# Mega_PCB.net
KiCad netlist of a schematic drawn in EAGLE
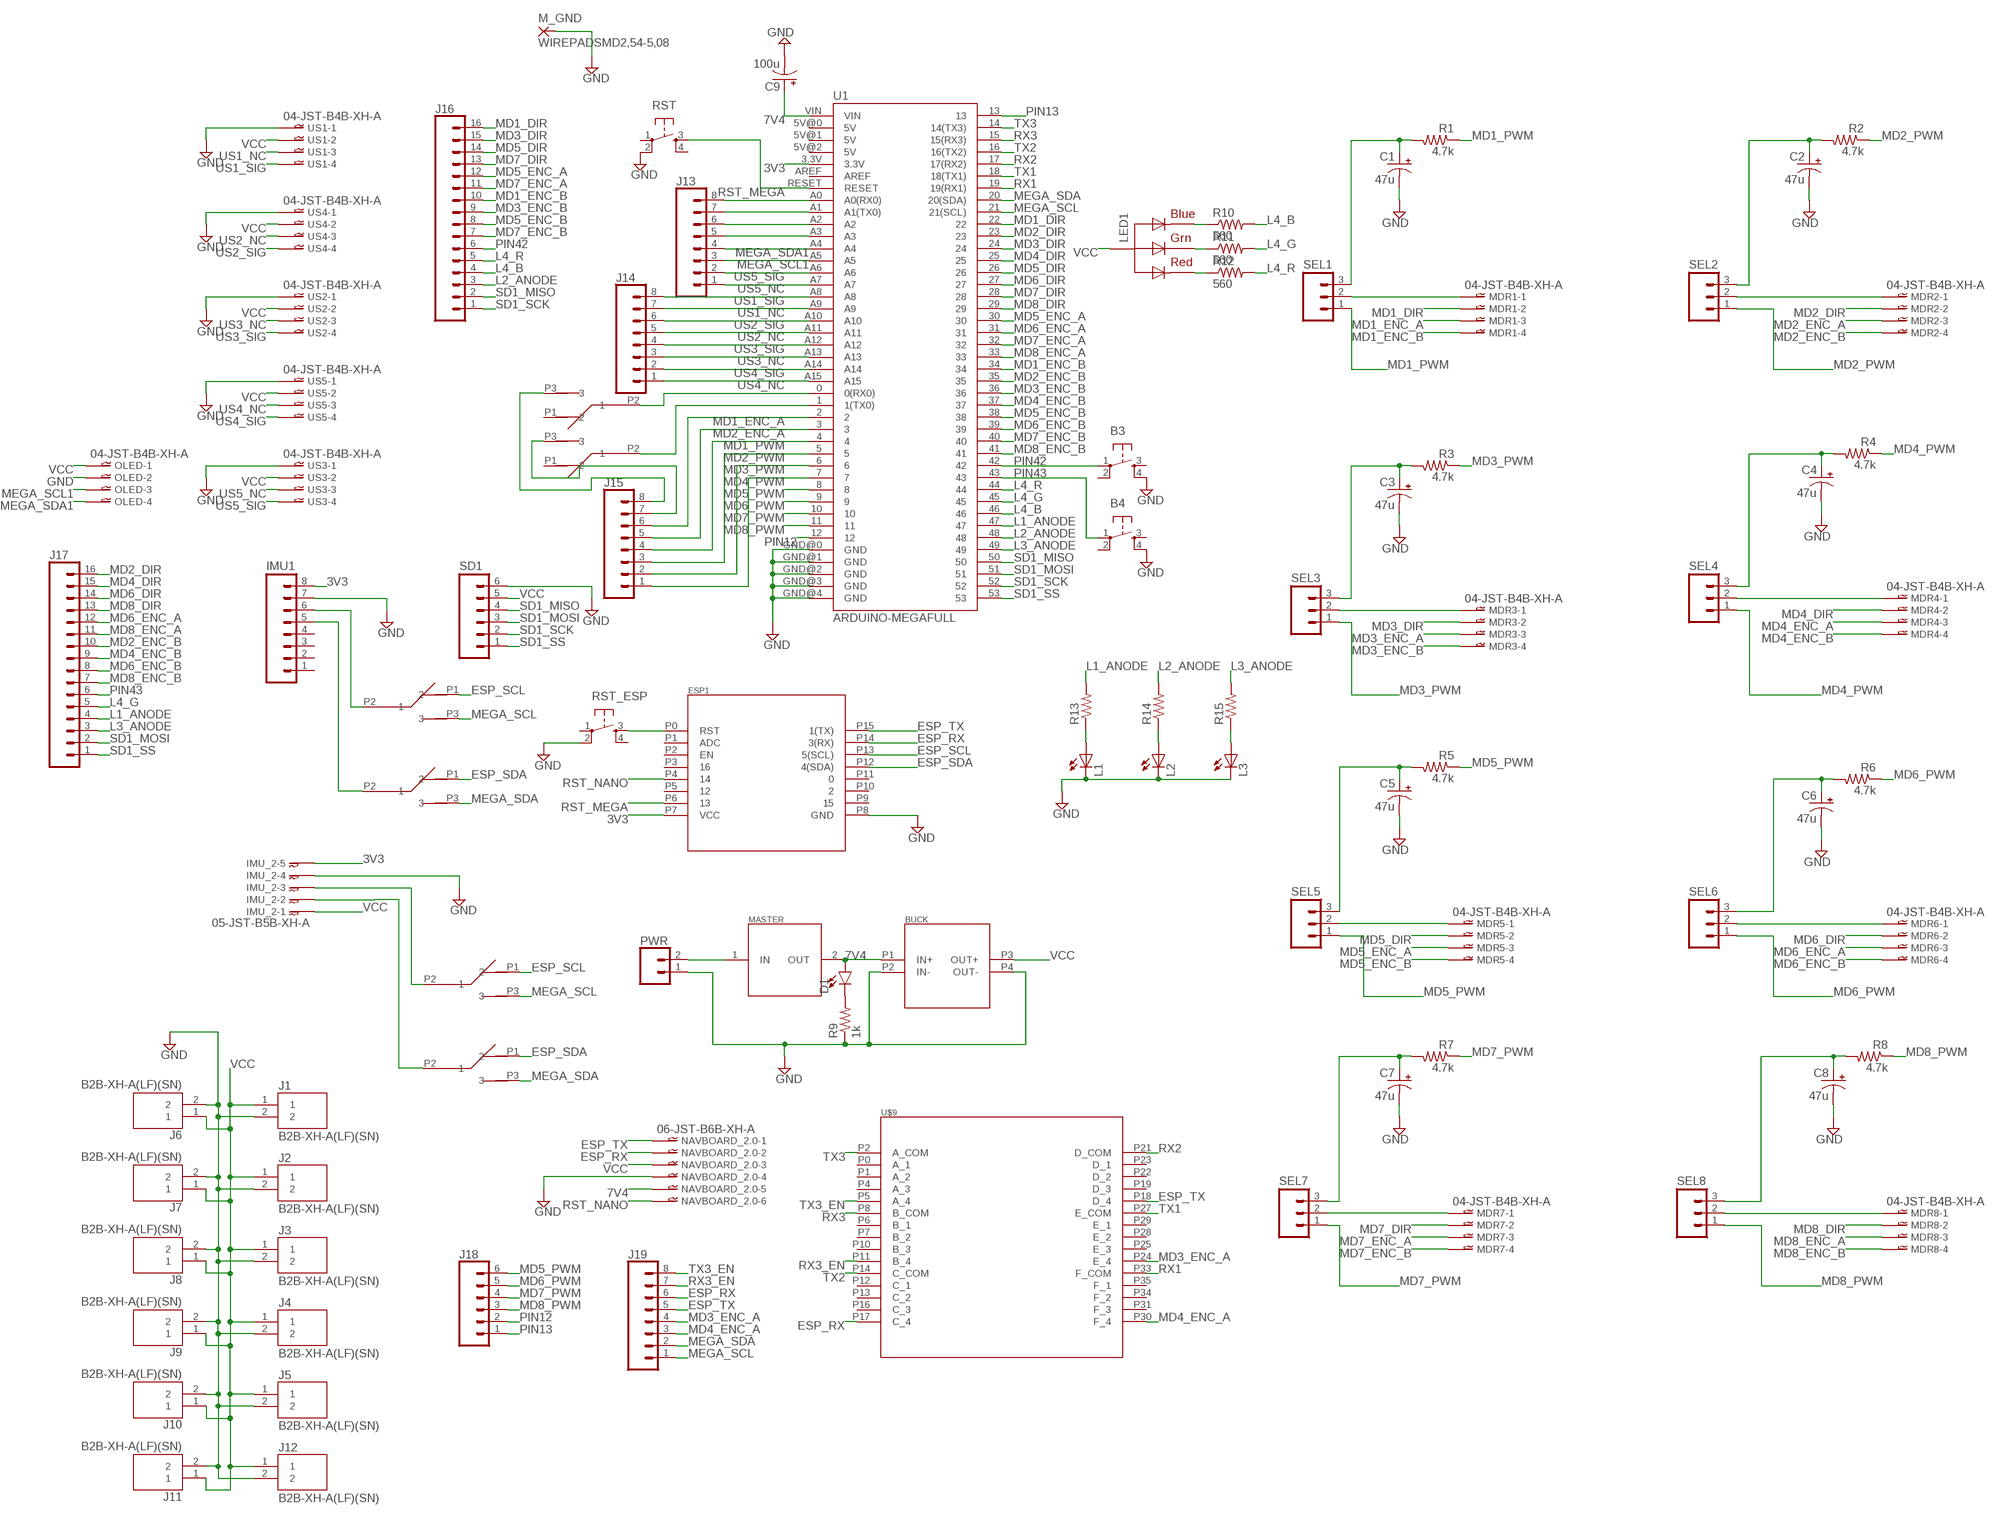
[diagram p0: schematic, sheet 1]

(export (version "E")
  (design (tool "Eeschema 10.0.6"))
  (components
    (comp (ref "B3")
      (value "TAC_SWITCHPTH")
      (footprint "eagle-import:TACTILE-PTH")
      (libsource (lib "eagle-import") (part "TAC_SWITCHPTH"))
    )
    (comp (ref "B4")
      (value "TAC_SWITCHPTH")
      (footprint "eagle-import:TACTILE-PTH")
      (libsource (lib "eagle-import") (part "TAC_SWITCHPTH"))
    )
    (comp (ref "BUCK")
      (value "5V_BUCK")
      (footprint "eagle-import:5V_BUCK")
      (libsource (lib "eagle-import") (part "5V_BUCK"))
    )
    (comp (ref "C1")
      (value "47u")
      (footprint "eagle-import:E2-5")
      (libsource (lib "eagle-import") (part "CPOL-USE2-5"))
    )
    (comp (ref "C2")
      (value "47u")
      (footprint "eagle-import:E2-5")
      (libsource (lib "eagle-import") (part "CPOL-USE2-5"))
    )
    (comp (ref "C3")
      (value "47u")
      (footprint "eagle-import:E2-5")
      (libsource (lib "eagle-import") (part "CPOL-USE2-5"))
    )
    (comp (ref "C4")
      (value "47u")
      (footprint "eagle-import:E2-5")
      (libsource (lib "eagle-import") (part "CPOL-USE2-5"))
    )
    (comp (ref "C5")
      (value "47u")
      (footprint "eagle-import:E2-5")
      (libsource (lib "eagle-import") (part "CPOL-USE2-5"))
    )
    (comp (ref "C6")
      (value "47u")
      (footprint "eagle-import:E2-5")
      (libsource (lib "eagle-import") (part "CPOL-USE2-5"))
    )
    (comp (ref "C7")
      (value "47u")
      (footprint "eagle-import:E2-5")
      (libsource (lib "eagle-import") (part "CPOL-USE2-5"))
    )
    (comp (ref "C8")
      (value "47u")
      (footprint "eagle-import:E2-5")
      (libsource (lib "eagle-import") (part "CPOL-USE2-5"))
    )
    (comp (ref "C9")
      (value "100u")
      (footprint "eagle-import:TT2D6")
      (libsource (lib "eagle-import") (part "CPOL-USTT2D6"))
    )
    (comp (ref "D1")
      (value "LED5MM")
      (footprint "eagle-import:LED_5MM")
      (libsource (lib "eagle-import") (part "LED5MM"))
    )
    (comp (ref "ESP1")
      (value "ESP07")
      (footprint "eagle-import:ESP07")
      (libsource (lib "eagle-import") (part "ESP07"))
    )
    (comp (ref "IMU1")
      (value "M081X08")
      (footprint "eagle-import:1X08")
      (libsource (lib "eagle-import") (part "M081X08"))
    )
    (comp (ref "IMU1_SCL_SEL")
      (value "SLIDE_SWITCH")
      (footprint "eagle-import:SLIDE_SWITCH")
      (libsource (lib "eagle-import") (part "SLIDE_SWITCH"))
    )
    (comp (ref "IMU1_SDA_SEL")
      (value "SLIDE_SWITCH")
      (footprint "eagle-import:SLIDE_SWITCH")
      (libsource (lib "eagle-import") (part "SLIDE_SWITCH"))
    )
    (comp (ref "IMU2_SCL_SEL")
      (value "SLIDE_SWITCH")
      (footprint "eagle-import:SLIDE_SWITCH")
      (libsource (lib "eagle-import") (part "SLIDE_SWITCH"))
    )
    (comp (ref "IMU2_SDA_SEL")
      (value "SLIDE_SWITCH")
      (footprint "eagle-import:SLIDE_SWITCH")
      (libsource (lib "eagle-import") (part "SLIDE_SWITCH"))
    )
    (comp (ref "IMU_2")
      (value "05-JST-B5B-XH-A")
      (footprint "eagle-import:B5B-XH")
      (libsource (lib "eagle-import") (part "05-JST-B5B-XH-A"))
    )
    (comp (ref "J1")
      (value "B2B-XH-A(LF)(SN)")
      (footprint "eagle-import:JST_B2B-XH-A(LF)(SN)")
      (fields (field (name "MF") "JST Sales"))
      (libsource (lib "eagle-import") (part "B2B-XH-A(LF)(SN)"))
    )
    (comp (ref "J2")
      (value "B2B-XH-A(LF)(SN)")
      (footprint "eagle-import:JST_B2B-XH-A(LF)(SN)")
      (fields (field (name "MF") "JST Sales"))
      (libsource (lib "eagle-import") (part "B2B-XH-A(LF)(SN)"))
    )
    (comp (ref "J3")
      (value "B2B-XH-A(LF)(SN)")
      (footprint "eagle-import:JST_B2B-XH-A(LF)(SN)")
      (fields (field (name "MF") "JST Sales"))
      (libsource (lib "eagle-import") (part "B2B-XH-A(LF)(SN)"))
    )
    (comp (ref "J4")
      (value "B2B-XH-A(LF)(SN)")
      (footprint "eagle-import:JST_B2B-XH-A(LF)(SN)")
      (fields (field (name "MF") "JST Sales"))
      (libsource (lib "eagle-import") (part "B2B-XH-A(LF)(SN)"))
    )
    (comp (ref "J5")
      (value "B2B-XH-A(LF)(SN)")
      (footprint "eagle-import:JST_B2B-XH-A(LF)(SN)")
      (fields (field (name "MF") "JST Sales"))
      (libsource (lib "eagle-import") (part "B2B-XH-A(LF)(SN)"))
    )
    (comp (ref "J6")
      (value "B2B-XH-A(LF)(SN)")
      (footprint "eagle-import:JST_B2B-XH-A(LF)(SN)")
      (fields (field (name "MF") "JST Sales"))
      (libsource (lib "eagle-import") (part "B2B-XH-A(LF)(SN)"))
    )
    (comp (ref "J7")
      (value "B2B-XH-A(LF)(SN)")
      (footprint "eagle-import:JST_B2B-XH-A(LF)(SN)")
      (fields (field (name "MF") "JST Sales"))
      (libsource (lib "eagle-import") (part "B2B-XH-A(LF)(SN)"))
    )
    (comp (ref "J8")
      (value "B2B-XH-A(LF)(SN)")
      (footprint "eagle-import:JST_B2B-XH-A(LF)(SN)")
      (fields (field (name "MF") "JST Sales"))
      (libsource (lib "eagle-import") (part "B2B-XH-A(LF)(SN)"))
    )
    (comp (ref "J9")
      (value "B2B-XH-A(LF)(SN)")
      (footprint "eagle-import:JST_B2B-XH-A(LF)(SN)")
      (fields (field (name "MF") "JST Sales"))
      (libsource (lib "eagle-import") (part "B2B-XH-A(LF)(SN)"))
    )
    (comp (ref "J10")
      (value "B2B-XH-A(LF)(SN)")
      (footprint "eagle-import:JST_B2B-XH-A(LF)(SN)")
      (fields (field (name "MF") "JST Sales"))
      (libsource (lib "eagle-import") (part "B2B-XH-A(LF)(SN)"))
    )
    (comp (ref "J11")
      (value "B2B-XH-A(LF)(SN)")
      (footprint "eagle-import:JST_B2B-XH-A(LF)(SN)")
      (fields (field (name "MF") "JST Sales"))
      (libsource (lib "eagle-import") (part "B2B-XH-A(LF)(SN)"))
    )
    (comp (ref "J12")
      (value "B2B-XH-A(LF)(SN)")
      (footprint "eagle-import:JST_B2B-XH-A(LF)(SN)")
      (fields (field (name "MF") "JST Sales"))
      (libsource (lib "eagle-import") (part "B2B-XH-A(LF)(SN)"))
    )
    (comp (ref "J13")
      (value "CONN_08\"")
      (footprint "eagle-import:1X08")
      (libsource (lib "eagle-import") (part "CONN_08{dblquote}"))
    )
    (comp (ref "J14")
      (value "CONN_08\"")
      (footprint "eagle-import:1X08")
      (libsource (lib "eagle-import") (part "CONN_08{dblquote}"))
    )
    (comp (ref "J15")
      (value "CONN_08\"")
      (footprint "eagle-import:1X08")
      (libsource (lib "eagle-import") (part "CONN_08{dblquote}"))
    )
    (comp (ref "J16")
      (value "CONN_16")
      (footprint "eagle-import:1X16")
      (libsource (lib "eagle-import") (part "CONN_16"))
    )
    (comp (ref "J17")
      (value "CONN_16")
      (footprint "eagle-import:1X16")
      (libsource (lib "eagle-import") (part "CONN_16"))
    )
    (comp (ref "J18")
      (value "CONN_06SILK_FEMALE_PTH")
      (footprint "eagle-import:1X06")
      (libsource (lib "eagle-import") (part "CONN_06SILK_FEMALE_PTH"))
    )
    (comp (ref "J19")
      (value "CONN_08\"")
      (footprint "eagle-import:1X08")
      (libsource (lib "eagle-import") (part "CONN_08{dblquote}"))
    )
    (comp (ref "L1")
      (value "LED3MM")
      (footprint "eagle-import:LED3MM")
      (libsource (lib "eagle-import") (part "adafruit_420_LED3MM"))
    )
    (comp (ref "L2")
      (value "LED3MM")
      (footprint "eagle-import:LED3MM")
      (libsource (lib "eagle-import") (part "adafruit_420_LED3MM"))
    )
    (comp (ref "L3")
      (value "LED3MM")
      (footprint "eagle-import:LED3MM")
      (libsource (lib "eagle-import") (part "adafruit_420_LED3MM"))
    )
    (comp (ref "LED1")
      (value "RGBLED_CA-5MM")
      (footprint "eagle-import:LED5MMRGB")
      (libsource (lib "eagle-import") (part "RGBLED_CA-5MM"))
    )
    (comp (ref "MASTER")
      (value "MED_SWITCH")
      (footprint "eagle-import:MED_SWITCH")
      (libsource (lib "eagle-import") (part "MED_SWITCH"))
    )
    (comp (ref "MDR1")
      (value "04-JST-B4B-XH-A")
      (footprint "eagle-import:B4B-XH")
      (libsource (lib "eagle-import") (part "04-JST-B4B-XH-A"))
    )
    (comp (ref "MDR2")
      (value "04-JST-B4B-XH-A")
      (footprint "eagle-import:B4B-XH")
      (libsource (lib "eagle-import") (part "04-JST-B4B-XH-A"))
    )
    (comp (ref "MDR3")
      (value "04-JST-B4B-XH-A")
      (footprint "eagle-import:B4B-XH")
      (libsource (lib "eagle-import") (part "04-JST-B4B-XH-A"))
    )
    (comp (ref "MDR4")
      (value "04-JST-B4B-XH-A")
      (footprint "eagle-import:B4B-XH")
      (libsource (lib "eagle-import") (part "04-JST-B4B-XH-A"))
    )
    (comp (ref "MDR5")
      (value "04-JST-B4B-XH-A")
      (footprint "eagle-import:B4B-XH")
      (libsource (lib "eagle-import") (part "04-JST-B4B-XH-A"))
    )
    (comp (ref "MDR6")
      (value "04-JST-B4B-XH-A")
      (footprint "eagle-import:B4B-XH")
      (libsource (lib "eagle-import") (part "04-JST-B4B-XH-A"))
    )
    (comp (ref "MDR7")
      (value "04-JST-B4B-XH-A")
      (footprint "eagle-import:B4B-XH")
      (libsource (lib "eagle-import") (part "04-JST-B4B-XH-A"))
    )
    (comp (ref "MDR8")
      (value "04-JST-B4B-XH-A")
      (footprint "eagle-import:B4B-XH")
      (libsource (lib "eagle-import") (part "04-JST-B4B-XH-A"))
    )
    (comp (ref "M_GND")
      (value "WIREPADSMD2,54-5,08")
      (footprint "eagle-import:SMD2,54-5,08")
      (libsource (lib "eagle-import") (part "WIREPADSMD2,54-5,08"))
    )
    (comp (ref "NAVBOARD_2.0")
      (value "06-JST-B6B-XH-A")
      (footprint "eagle-import:B6B-XH")
      (libsource (lib "eagle-import") (part "06-JST-B6B-XH-A"))
    )
    (comp (ref "OLED")
      (value "04-JST-B4B-XH-A")
      (footprint "eagle-import:B4B-XH")
      (libsource (lib "eagle-import") (part "04-JST-B4B-XH-A"))
    )
    (comp (ref "PWR")
      (value "CONN_02PTH4")
      (footprint "eagle-import:1X02_XTRA_BIG")
      (libsource (lib "eagle-import") (part "CONN_02PTH4"))
    )
    (comp (ref "R1")
      (value "4.7k")
      (footprint "eagle-import:0204_7")
      (libsource (lib "eagle-import") (part "R-US_0204/7"))
    )
    (comp (ref "R2")
      (value "4.7k")
      (footprint "eagle-import:0204_7")
      (libsource (lib "eagle-import") (part "R-US_0204/7"))
    )
    (comp (ref "R3")
      (value "4.7k")
      (footprint "eagle-import:0204_7")
      (libsource (lib "eagle-import") (part "R-US_0204/7"))
    )
    (comp (ref "R4")
      (value "4.7k")
      (footprint "eagle-import:0204_7")
      (libsource (lib "eagle-import") (part "R-US_0204/7"))
    )
    (comp (ref "R5")
      (value "4.7k")
      (footprint "eagle-import:0204_7")
      (libsource (lib "eagle-import") (part "R-US_0204/7"))
    )
    (comp (ref "R6")
      (value "4.7k")
      (footprint "eagle-import:0204_7")
      (libsource (lib "eagle-import") (part "R-US_0204/7"))
    )
    (comp (ref "R7")
      (value "4.7k")
      (footprint "eagle-import:0204_7")
      (libsource (lib "eagle-import") (part "R-US_0204/7"))
    )
    (comp (ref "R8")
      (value "4.7k")
      (footprint "eagle-import:0204_7")
      (libsource (lib "eagle-import") (part "R-US_0204/7"))
    )
    (comp (ref "R9")
      (value "1k")
      (footprint "eagle-import:0204_7")
      (libsource (lib "eagle-import") (part "R-US_0204/7"))
    )
    (comp (ref "R10")
      (value "560")
      (footprint "eagle-import:0204_7")
      (libsource (lib "eagle-import") (part "R-US_0204/7"))
    )
    (comp (ref "R11")
      (value "560")
      (footprint "eagle-import:0204_7")
      (libsource (lib "eagle-import") (part "R-US_0204/7"))
    )
    (comp (ref "R12")
      (value "560")
      (footprint "eagle-import:0204_7")
      (libsource (lib "eagle-import") (part "R-US_0204/7"))
    )
    (comp (ref "R13")
      (value "R-US_0204/7")
      (footprint "eagle-import:0204_7")
      (libsource (lib "eagle-import") (part "R-US_0204/7"))
    )
    (comp (ref "R14")
      (value "R-US_0204/7")
      (footprint "eagle-import:0204_7")
      (libsource (lib "eagle-import") (part "R-US_0204/7"))
    )
    (comp (ref "R15")
      (value "R-US_0204/7")
      (footprint "eagle-import:0204_7")
      (libsource (lib "eagle-import") (part "R-US_0204/7"))
    )
    (comp (ref "RST")
      (value "TAC_SWITCHPTH")
      (footprint "eagle-import:TACTILE-PTH")
      (libsource (lib "eagle-import") (part "TAC_SWITCHPTH"))
    )
    (comp (ref "RST_ESP")
      (value "TAC_SWITCHPTH")
      (footprint "eagle-import:TACTILE-PTH")
      (libsource (lib "eagle-import") (part "TAC_SWITCHPTH"))
    )
    (comp (ref "SD1")
      (value "M06SIP")
      (footprint "eagle-import:1X06")
      (libsource (lib "eagle-import") (part "M06SIP"))
    )
    (comp (ref "SEL1")
      (value "M03PTH")
      (footprint "eagle-import:1X03")
      (libsource (lib "eagle-import") (part "M03PTH"))
    )
    (comp (ref "SEL2")
      (value "M03PTH")
      (footprint "eagle-import:1X03")
      (libsource (lib "eagle-import") (part "M03PTH"))
    )
    (comp (ref "SEL3")
      (value "M03PTH")
      (footprint "eagle-import:1X03")
      (libsource (lib "eagle-import") (part "M03PTH"))
    )
    (comp (ref "SEL4")
      (value "M03PTH")
      (footprint "eagle-import:1X03")
      (libsource (lib "eagle-import") (part "M03PTH"))
    )
    (comp (ref "SEL5")
      (value "M03PTH")
      (footprint "eagle-import:1X03")
      (libsource (lib "eagle-import") (part "M03PTH"))
    )
    (comp (ref "SEL6")
      (value "M03PTH")
      (footprint "eagle-import:1X03")
      (libsource (lib "eagle-import") (part "M03PTH"))
    )
    (comp (ref "SEL7")
      (value "M03PTH")
      (footprint "eagle-import:1X03")
      (libsource (lib "eagle-import") (part "M03PTH"))
    )
    (comp (ref "SEL8")
      (value "M03PTH")
      (footprint "eagle-import:1X03")
      (libsource (lib "eagle-import") (part "M03PTH"))
    )
    (comp (ref "U$3")
      (value "SLIDE_SWITCH")
      (footprint "eagle-import:SLIDE_SWITCH")
      (libsource (lib "eagle-import") (part "SLIDE_SWITCH"))
    )
    (comp (ref "U$4")
      (value "SLIDE_SWITCH")
      (footprint "eagle-import:SLIDE_SWITCH")
      (libsource (lib "eagle-import") (part "SLIDE_SWITCH"))
    )
    (comp (ref "U$9")
      (value "CATERPILLAR")
      (footprint "eagle-import:CATERPILLAR")
      (libsource (lib "eagle-import") (part "CATERPILLAR"))
    )
    (comp (ref "U1")
      (value "ARDUINO-MEGAFULL")
      (footprint "eagle-import:ARDUINO_MEGA")
      (libsource (lib "eagle-import") (part "ARDUINO-MEGAFULL"))
    )
    (comp (ref "US1")
      (value "04-JST-B4B-XH-A")
      (footprint "eagle-import:B4B-XH")
      (libsource (lib "eagle-import") (part "04-JST-B4B-XH-A"))
    )
    (comp (ref "US2")
      (value "04-JST-B4B-XH-A")
      (footprint "eagle-import:B4B-XH")
      (libsource (lib "eagle-import") (part "04-JST-B4B-XH-A"))
    )
    (comp (ref "US3")
      (value "04-JST-B4B-XH-A")
      (footprint "eagle-import:B4B-XH")
      (libsource (lib "eagle-import") (part "04-JST-B4B-XH-A"))
    )
    (comp (ref "US4")
      (value "04-JST-B4B-XH-A")
      (footprint "eagle-import:B4B-XH")
      (libsource (lib "eagle-import") (part "04-JST-B4B-XH-A"))
    )
    (comp (ref "US5")
      (value "04-JST-B4B-XH-A")
      (footprint "eagle-import:B4B-XH")
      (libsource (lib "eagle-import") (part "04-JST-B4B-XH-A"))
    )
  )
  (nets
    (net (code "1") (name "/3V3") (class "Default")
      (node (ref "ESP1") (pin "P7") (pinfunction "VCC_P7") (pintype "bidirectional"))
      (node (ref "IMU1") (pin "8") (pinfunction "8_8") (pintype "passive"))
      (node (ref "IMU_2") (pin "P$5") (pinfunction "1_P$5") (pintype "passive"))
      (node (ref "U1") (pin "3.3V") (pinfunction "3.3V_3.3V") (pintype "bidirectional"))
    )
    (net (code "2") (name "/7V4") (class "Default")
      (node (ref "BUCK") (pin "P1") (pinfunction "IN+_P1") (pintype "bidirectional"))
      (node (ref "C9") (pin "+") (pinfunction "+_+") (pintype "passive"))
      (node (ref "D1") (pin "A") (pinfunction "A_A") (pintype "passive"))
      (node (ref "MASTER") (pin "2") (pinfunction "OUT_2") (pintype "bidirectional"))
      (node (ref "NAVBOARD_2.0") (pin "P$5") (pinfunction "1_P$5") (pintype "passive"))
      (node (ref "U1") (pin "VIN") (pinfunction "VIN_VIN") (pintype "bidirectional"))
    )
    (net (code "3") (name "/ESP_RX") (class "Default")
      (node (ref "ESP1") (pin "P14") (pinfunction "3(RX)_P14") (pintype "bidirectional"))
      (node (ref "J19") (pin "6") (pinfunction "6_6") (pintype "passive"))
      (node (ref "NAVBOARD_2.0") (pin "P$2") (pinfunction "1_P$2") (pintype "passive"))
      (node (ref "U$9") (pin "P17") (pinfunction "C_4_P17") (pintype "bidirectional"))
    )
    (net (code "4") (name "/ESP_SCL") (class "Default")
      (node (ref "ESP1") (pin "P13") (pinfunction "5(SCL)_P13") (pintype "bidirectional"))
      (node (ref "IMU1_SCL_SEL") (pin "P1") (pinfunction "2_P1") (pintype "bidirectional"))
      (node (ref "IMU2_SCL_SEL") (pin "P1") (pinfunction "2_P1") (pintype "bidirectional"))
    )
    (net (code "5") (name "/ESP_SDA") (class "Default")
      (node (ref "ESP1") (pin "P12") (pinfunction "4(SDA)_P12") (pintype "bidirectional"))
      (node (ref "IMU1_SDA_SEL") (pin "P1") (pinfunction "2_P1") (pintype "bidirectional"))
      (node (ref "IMU2_SDA_SEL") (pin "P1") (pinfunction "2_P1") (pintype "bidirectional"))
    )
    (net (code "6") (name "/ESP_TX") (class "Default")
      (node (ref "ESP1") (pin "P15") (pinfunction "1(TX)_P15") (pintype "bidirectional"))
      (node (ref "J19") (pin "5") (pinfunction "5_5") (pintype "passive"))
      (node (ref "NAVBOARD_2.0") (pin "P$1") (pinfunction "1_P$1") (pintype "passive"))
      (node (ref "U$9") (pin "P18") (pinfunction "D_4_P18") (pintype "bidirectional"))
    )
    (net (code "7") (name "/L1_ANODE") (class "Default")
      (node (ref "J17") (pin "4") (pinfunction "4_4") (pintype "passive"))
      (node (ref "R13") (pin "2") (pinfunction "2_2") (pintype "passive"))
      (node (ref "U1") (pin "47") (pinfunction "47_47") (pintype "bidirectional"))
    )
    (net (code "8") (name "/L2_ANODE") (class "Default")
      (node (ref "J16") (pin "3") (pinfunction "3_3") (pintype "passive"))
      (node (ref "R14") (pin "2") (pinfunction "2_2") (pintype "passive"))
      (node (ref "U1") (pin "48") (pinfunction "48_48") (pintype "bidirectional"))
    )
    (net (code "9") (name "/L3_ANODE") (class "Default")
      (node (ref "J17") (pin "3") (pinfunction "3_3") (pintype "passive"))
      (node (ref "R15") (pin "2") (pinfunction "2_2") (pintype "passive"))
      (node (ref "U1") (pin "49") (pinfunction "49_49") (pintype "bidirectional"))
    )
    (net (code "10") (name "/L4_B") (class "Default")
      (node (ref "J16") (pin "4") (pinfunction "4_4") (pintype "passive"))
      (node (ref "R10") (pin "2") (pinfunction "2_2") (pintype "passive"))
      (node (ref "U1") (pin "46") (pinfunction "46_46") (pintype "bidirectional"))
    )
    (net (code "11") (name "/L4_G") (class "Default")
      (node (ref "J17") (pin "5") (pinfunction "5_5") (pintype "passive"))
      (node (ref "R11") (pin "2") (pinfunction "2_2") (pintype "passive"))
      (node (ref "U1") (pin "45") (pinfunction "45_45") (pintype "bidirectional"))
    )
    (net (code "12") (name "/L4_R") (class "Default")
      (node (ref "J16") (pin "5") (pinfunction "5_5") (pintype "passive"))
      (node (ref "R12") (pin "2") (pinfunction "2_2") (pintype "passive"))
      (node (ref "U1") (pin "44") (pinfunction "44_44") (pintype "bidirectional"))
    )
    (net (code "13") (name "/MD1_DIR") (class "Default")
      (node (ref "J16") (pin "16") (pinfunction "16_16") (pintype "passive"))
      (node (ref "MDR1") (pin "P$2") (pinfunction "1_P$2") (pintype "passive"))
      (node (ref "U1") (pin "22") (pinfunction "22_22") (pintype "bidirectional"))
    )
    (net (code "14") (name "/MD1_ENC_A") (class "Default")
      (node (ref "J15") (pin "6") (pinfunction "6_6") (pintype "passive"))
      (node (ref "MDR1") (pin "P$3") (pinfunction "1_P$3") (pintype "passive"))
      (node (ref "U1") (pin "2") (pinfunction "2_2") (pintype "bidirectional"))
    )
    (net (code "15") (name "/MD1_ENC_B") (class "Default")
      (node (ref "J16") (pin "10") (pinfunction "10_10") (pintype "passive"))
      (node (ref "MDR1") (pin "P$4") (pinfunction "1_P$4") (pintype "passive"))
      (node (ref "U1") (pin "34") (pinfunction "34_34") (pintype "bidirectional"))
    )
    (net (code "16") (name "/MD1_PWM") (class "Default")
      (node (ref "J15") (pin "4") (pinfunction "4_4") (pintype "passive"))
      (node (ref "R1") (pin "1") (pinfunction "1_1") (pintype "passive"))
      (node (ref "SEL1") (pin "1") (pinfunction "1_1") (pintype "passive"))
      (node (ref "U1") (pin "4") (pinfunction "4_4") (pintype "bidirectional"))
    )
    (net (code "17") (name "/MD2_DIR") (class "Default")
      (node (ref "J17") (pin "16") (pinfunction "16_16") (pintype "passive"))
      (node (ref "MDR2") (pin "P$2") (pinfunction "1_P$2") (pintype "passive"))
      (node (ref "U1") (pin "23") (pinfunction "23_23") (pintype "bidirectional"))
    )
    (net (code "18") (name "/MD2_ENC_A") (class "Default")
      (node (ref "J15") (pin "5") (pinfunction "5_5") (pintype "passive"))
      (node (ref "MDR2") (pin "P$3") (pinfunction "1_P$3") (pintype "passive"))
      (node (ref "U1") (pin "3") (pinfunction "3_3") (pintype "bidirectional"))
    )
    (net (code "19") (name "/MD2_ENC_B") (class "Default")
      (node (ref "J17") (pin "10") (pinfunction "10_10") (pintype "passive"))
      (node (ref "MDR2") (pin "P$4") (pinfunction "1_P$4") (pintype "passive"))
      (node (ref "U1") (pin "35") (pinfunction "35_35") (pintype "bidirectional"))
    )
    (net (code "20") (name "/MD2_PWM") (class "Default")
      (node (ref "J15") (pin "3") (pinfunction "3_3") (pintype "passive"))
      (node (ref "R2") (pin "1") (pinfunction "1_1") (pintype "passive"))
      (node (ref "SEL2") (pin "1") (pinfunction "1_1") (pintype "passive"))
      (node (ref "U1") (pin "5") (pinfunction "5_5") (pintype "bidirectional"))
    )
    (net (code "21") (name "/MD3_DIR") (class "Default")
      (node (ref "J16") (pin "15") (pinfunction "15_15") (pintype "passive"))
      (node (ref "MDR3") (pin "P$2") (pinfunction "1_P$2") (pintype "passive"))
      (node (ref "U1") (pin "24") (pinfunction "24_24") (pintype "bidirectional"))
    )
    (net (code "22") (name "/MD3_ENC_A") (class "Default")
      (node (ref "J19") (pin "4") (pinfunction "4_4") (pintype "passive"))
      (node (ref "MDR3") (pin "P$3") (pinfunction "1_P$3") (pintype "passive"))
      (node (ref "U$9") (pin "P24") (pinfunction "E_4_P24") (pintype "bidirectional"))
    )
    (net (code "23") (name "/MD3_ENC_B") (class "Default")
      (node (ref "J16") (pin "9") (pinfunction "9_9") (pintype "passive"))
      (node (ref "MDR3") (pin "P$4") (pinfunction "1_P$4") (pintype "passive"))
      (node (ref "U1") (pin "36") (pinfunction "36_36") (pintype "bidirectional"))
    )
    (net (code "24") (name "/MD3_PWM") (class "Default")
      (node (ref "J15") (pin "2") (pinfunction "2_2") (pintype "passive"))
      (node (ref "R3") (pin "1") (pinfunction "1_1") (pintype "passive"))
      (node (ref "SEL3") (pin "1") (pinfunction "1_1") (pintype "passive"))
      (node (ref "U1") (pin "6") (pinfunction "6_6") (pintype "bidirectional"))
    )
    (net (code "25") (name "/MD4_DIR") (class "Default")
      (node (ref "J17") (pin "15") (pinfunction "15_15") (pintype "passive"))
      (node (ref "MDR4") (pin "P$2") (pinfunction "1_P$2") (pintype "passive"))
      (node (ref "U1") (pin "25") (pinfunction "25_25") (pintype "bidirectional"))
    )
    (net (code "26") (name "/MD4_ENC_A") (class "Default")
      (node (ref "J19") (pin "3") (pinfunction "3_3") (pintype "passive"))
      (node (ref "MDR4") (pin "P$3") (pinfunction "1_P$3") (pintype "passive"))
      (node (ref "U$9") (pin "P30") (pinfunction "F_4_P30") (pintype "bidirectional"))
    )
    (net (code "27") (name "/MD4_ENC_B") (class "Default")
      (node (ref "J17") (pin "9") (pinfunction "9_9") (pintype "passive"))
      (node (ref "MDR4") (pin "P$4") (pinfunction "1_P$4") (pintype "passive"))
      (node (ref "U1") (pin "37") (pinfunction "37_37") (pintype "bidirectional"))
    )
    (net (code "28") (name "/MD4_PWM") (class "Default")
      (node (ref "J15") (pin "1") (pinfunction "1_1") (pintype "passive"))
      (node (ref "R4") (pin "1") (pinfunction "1_1") (pintype "passive"))
      (node (ref "SEL4") (pin "1") (pinfunction "1_1") (pintype "passive"))
      (node (ref "U1") (pin "7") (pinfunction "7_7") (pintype "bidirectional"))
    )
    (net (code "29") (name "/MD5_DIR") (class "Default")
      (node (ref "J16") (pin "14") (pinfunction "14_14") (pintype "passive"))
      (node (ref "MDR5") (pin "P$2") (pinfunction "1_P$2") (pintype "passive"))
      (node (ref "U1") (pin "26") (pinfunction "26_26") (pintype "bidirectional"))
    )
    (net (code "30") (name "/MD5_ENC_A") (class "Default")
      (node (ref "J16") (pin "12") (pinfunction "12_12") (pintype "passive"))
      (node (ref "MDR5") (pin "P$3") (pinfunction "1_P$3") (pintype "passive"))
      (node (ref "U1") (pin "30") (pinfunction "30_30") (pintype "bidirectional"))
    )
    (net (code "31") (name "/MD5_ENC_B") (class "Default")
      (node (ref "J16") (pin "8") (pinfunction "8_8") (pintype "passive"))
      (node (ref "MDR5") (pin "P$4") (pinfunction "1_P$4") (pintype "passive"))
      (node (ref "U1") (pin "38") (pinfunction "38_38") (pintype "bidirectional"))
    )
    (net (code "32") (name "/MD5_PWM") (class "Default")
      (node (ref "J18") (pin "6") (pinfunction "6_6") (pintype "passive"))
      (node (ref "R5") (pin "1") (pinfunction "1_1") (pintype "passive"))
      (node (ref "SEL5") (pin "1") (pinfunction "1_1") (pintype "passive"))
      (node (ref "U1") (pin "8") (pinfunction "8_8") (pintype "bidirectional"))
    )
    (net (code "33") (name "/MD6_DIR") (class "Default")
      (node (ref "J17") (pin "14") (pinfunction "14_14") (pintype "passive"))
      (node (ref "MDR6") (pin "P$2") (pinfunction "1_P$2") (pintype "passive"))
      (node (ref "U1") (pin "27") (pinfunction "27_27") (pintype "bidirectional"))
    )
    (net (code "34") (name "/MD6_ENC_A") (class "Default")
      (node (ref "J17") (pin "12") (pinfunction "12_12") (pintype "passive"))
      (node (ref "MDR6") (pin "P$3") (pinfunction "1_P$3") (pintype "passive"))
      (node (ref "U1") (pin "31") (pinfunction "31_31") (pintype "bidirectional"))
    )
    (net (code "35") (name "/MD6_ENC_B") (class "Default")
      (node (ref "J17") (pin "8") (pinfunction "8_8") (pintype "passive"))
      (node (ref "MDR6") (pin "P$4") (pinfunction "1_P$4") (pintype "passive"))
      (node (ref "U1") (pin "39") (pinfunction "39_39") (pintype "bidirectional"))
    )
    (net (code "36") (name "/MD6_PWM") (class "Default")
      (node (ref "J18") (pin "5") (pinfunction "5_5") (pintype "passive"))
      (node (ref "R6") (pin "1") (pinfunction "1_1") (pintype "passive"))
      (node (ref "SEL6") (pin "1") (pinfunction "1_1") (pintype "passive"))
      (node (ref "U1") (pin "9") (pinfunction "9_9") (pintype "bidirectional"))
    )
    (net (code "37") (name "/MD7_DIR") (class "Default")
      (node (ref "J16") (pin "13") (pinfunction "13_13") (pintype "passive"))
      (node (ref "MDR7") (pin "P$2") (pinfunction "1_P$2") (pintype "passive"))
      (node (ref "U1") (pin "28") (pinfunction "28_28") (pintype "bidirectional"))
    )
    (net (code "38") (name "/MD7_ENC_A") (class "Default")
      (node (ref "J16") (pin "11") (pinfunction "11_11") (pintype "passive"))
      (node (ref "MDR7") (pin "P$3") (pinfunction "1_P$3") (pintype "passive"))
      (node (ref "U1") (pin "32") (pinfunction "32_32") (pintype "bidirectional"))
    )
    (net (code "39") (name "/MD7_ENC_B") (class "Default")
      (node (ref "J16") (pin "7") (pinfunction "7_7") (pintype "passive"))
      (node (ref "MDR7") (pin "P$4") (pinfunction "1_P$4") (pintype "passive"))
      (node (ref "U1") (pin "40") (pinfunction "40_40") (pintype "bidirectional"))
    )
    (net (code "40") (name "/MD7_PWM") (class "Default")
      (node (ref "J18") (pin "4") (pinfunction "4_4") (pintype "passive"))
      (node (ref "R7") (pin "1") (pinfunction "1_1") (pintype "passive"))
      (node (ref "SEL7") (pin "1") (pinfunction "1_1") (pintype "passive"))
      (node (ref "U1") (pin "10") (pinfunction "10_10") (pintype "bidirectional"))
    )
    (net (code "41") (name "/MD8_DIR") (class "Default")
      (node (ref "J17") (pin "13") (pinfunction "13_13") (pintype "passive"))
      (node (ref "MDR8") (pin "P$2") (pinfunction "1_P$2") (pintype "passive"))
      (node (ref "U1") (pin "29") (pinfunction "29_29") (pintype "bidirectional"))
    )
    (net (code "42") (name "/MD8_ENC_A") (class "Default")
      (node (ref "J17") (pin "11") (pinfunction "11_11") (pintype "passive"))
      (node (ref "MDR8") (pin "P$3") (pinfunction "1_P$3") (pintype "passive"))
      (node (ref "U1") (pin "33") (pinfunction "33_33") (pintype "bidirectional"))
    )
    (net (code "43") (name "/MD8_ENC_B") (class "Default")
      (node (ref "J17") (pin "7") (pinfunction "7_7") (pintype "passive"))
      (node (ref "MDR8") (pin "P$4") (pinfunction "1_P$4") (pintype "passive"))
      (node (ref "U1") (pin "41") (pinfunction "41_41") (pintype "bidirectional"))
    )
    (net (code "44") (name "/MD8_PWM") (class "Default")
      (node (ref "J18") (pin "3") (pinfunction "3_3") (pintype "passive"))
      (node (ref "R8") (pin "1") (pinfunction "1_1") (pintype "passive"))
      (node (ref "SEL8") (pin "1") (pinfunction "1_1") (pintype "passive"))
      (node (ref "U1") (pin "11") (pinfunction "11_11") (pintype "bidirectional"))
    )
    (net (code "45") (name "/MEGA_SCL") (class "Default")
      (node (ref "IMU1_SCL_SEL") (pin "P3") (pinfunction "3_P3") (pintype "bidirectional"))
      (node (ref "IMU2_SCL_SEL") (pin "P3") (pinfunction "3_P3") (pintype "bidirectional"))
      (node (ref "J19") (pin "1") (pinfunction "1_1") (pintype "passive"))
      (node (ref "U1") (pin "21") (pinfunction "21(SCL)_21") (pintype "bidirectional"))
    )
    (net (code "46") (name "/MEGA_SCL1") (class "Default")
      (node (ref "J13") (pin "3") (pinfunction "3_3") (pintype "passive"))
      (node (ref "OLED") (pin "P$3") (pinfunction "1_P$3") (pintype "passive"))
      (node (ref "U1") (pin "A5") (pinfunction "A5_A5") (pintype "bidirectional"))
    )
    (net (code "47") (name "/MEGA_SDA") (class "Default")
      (node (ref "IMU1_SDA_SEL") (pin "P3") (pinfunction "3_P3") (pintype "bidirectional"))
      (node (ref "IMU2_SDA_SEL") (pin "P3") (pinfunction "3_P3") (pintype "bidirectional"))
      (node (ref "J19") (pin "2") (pinfunction "2_2") (pintype "passive"))
      (node (ref "U1") (pin "20") (pinfunction "20(SDA)_20") (pintype "bidirectional"))
    )
    (net (code "48") (name "/MEGA_SDA1") (class "Default")
      (node (ref "J13") (pin "4") (pinfunction "4_4") (pintype "passive"))
      (node (ref "OLED") (pin "P$4") (pinfunction "1_P$4") (pintype "passive"))
      (node (ref "U1") (pin "A4") (pinfunction "A4_A4") (pintype "bidirectional"))
    )
    (net (code "49") (name "/PIN12") (class "Default")
      (node (ref "J18") (pin "2") (pinfunction "2_2") (pintype "passive"))
      (node (ref "U1") (pin "12") (pinfunction "12_12") (pintype "bidirectional"))
    )
    (net (code "50") (name "/PIN13") (class "Default")
      (node (ref "J18") (pin "1") (pinfunction "1_1") (pintype "passive"))
      (node (ref "U1") (pin "13") (pinfunction "13_13") (pintype "bidirectional"))
    )
    (net (code "51") (name "/PIN42") (class "Default")
      (node (ref "B3") (pin "1") (pinfunction "1_1") (pintype "passive"))
      (node (ref "J16") (pin "6") (pinfunction "6_6") (pintype "passive"))
      (node (ref "U1") (pin "42") (pinfunction "42_42") (pintype "bidirectional"))
    )
    (net (code "52") (name "/PIN43") (class "Default")
      (node (ref "B4") (pin "1") (pinfunction "1_1") (pintype "passive"))
      (node (ref "J17") (pin "6") (pinfunction "6_6") (pintype "passive"))
      (node (ref "U1") (pin "43") (pinfunction "43_43") (pintype "bidirectional"))
    )
    (net (code "53") (name "/RST_MEGA") (class "Default")
      (node (ref "ESP1") (pin "P6") (pinfunction "13_P6") (pintype "bidirectional"))
      (node (ref "RST") (pin "3") (pinfunction "3_3") (pintype "passive"))
      (node (ref "U1") (pin "RESET") (pinfunction "RESET_RESET") (pintype "bidirectional"))
    )
    (net (code "54") (name "/RST_NANO") (class "Default")
      (node (ref "ESP1") (pin "P4") (pinfunction "14_P4") (pintype "bidirectional"))
      (node (ref "NAVBOARD_2.0") (pin "P$6") (pinfunction "1_P$6") (pintype "passive"))
    )
    (net (code "55") (name "/RX1") (class "Default")
      (node (ref "U$9") (pin "P33") (pinfunction "F_COM_P33") (pintype "bidirectional"))
      (node (ref "U1") (pin "19") (pinfunction "19(RX1)_19") (pintype "bidirectional"))
    )
    (net (code "56") (name "/RX2") (class "Default")
      (node (ref "U$9") (pin "P21") (pinfunction "D_COM_P21") (pintype "bidirectional"))
      (node (ref "U1") (pin "17") (pinfunction "17(RX2)_17") (pintype "bidirectional"))
    )
    (net (code "57") (name "/RX3") (class "Default")
      (node (ref "U$9") (pin "P8") (pinfunction "B_COM_P8") (pintype "bidirectional"))
      (node (ref "U1") (pin "15") (pinfunction "15(RX3)_15") (pintype "bidirectional"))
    )
    (net (code "58") (name "/RX3_EN") (class "Default")
      (node (ref "J19") (pin "7") (pinfunction "7_7") (pintype "passive"))
      (node (ref "U$9") (pin "P11") (pinfunction "B_4_P11") (pintype "bidirectional"))
    )
    (net (code "59") (name "/SD1_MISO") (class "Default")
      (node (ref "J16") (pin "2") (pinfunction "2_2") (pintype "passive"))
      (node (ref "SD1") (pin "4") (pinfunction "4_4") (pintype "passive"))
      (node (ref "U1") (pin "50") (pinfunction "50_50") (pintype "bidirectional"))
    )
    (net (code "60") (name "/SD1_MOSI") (class "Default")
      (node (ref "J17") (pin "2") (pinfunction "2_2") (pintype "passive"))
      (node (ref "SD1") (pin "3") (pinfunction "3_3") (pintype "passive"))
      (node (ref "U1") (pin "51") (pinfunction "51_51") (pintype "bidirectional"))
    )
    (net (code "61") (name "/SD1_SCK") (class "Default")
      (node (ref "J16") (pin "1") (pinfunction "1_1") (pintype "passive"))
      (node (ref "SD1") (pin "2") (pinfunction "2_2") (pintype "passive"))
      (node (ref "U1") (pin "52") (pinfunction "52_52") (pintype "bidirectional"))
    )
    (net (code "62") (name "/SD1_SS") (class "Default")
      (node (ref "J17") (pin "1") (pinfunction "1_1") (pintype "passive"))
      (node (ref "SD1") (pin "1") (pinfunction "1_1") (pintype "passive"))
      (node (ref "U1") (pin "53") (pinfunction "53_53") (pintype "bidirectional"))
    )
    (net (code "63") (name "/TX1") (class "Default")
      (node (ref "U$9") (pin "P27") (pinfunction "E_COM_P27") (pintype "bidirectional"))
      (node (ref "U1") (pin "18") (pinfunction "18(TX1)_18") (pintype "bidirectional"))
    )
    (net (code "64") (name "/TX2") (class "Default")
      (node (ref "U$9") (pin "P14") (pinfunction "C_COM_P14") (pintype "bidirectional"))
      (node (ref "U1") (pin "16") (pinfunction "16(TX2)_16") (pintype "bidirectional"))
    )
    (net (code "65") (name "/TX3") (class "Default")
      (node (ref "U$9") (pin "P2") (pinfunction "A_COM_P2") (pintype "bidirectional"))
      (node (ref "U1") (pin "14") (pinfunction "14(TX3)_14") (pintype "bidirectional"))
    )
    (net (code "66") (name "/TX3_EN") (class "Default")
      (node (ref "J19") (pin "8") (pinfunction "8_8") (pintype "passive"))
      (node (ref "U$9") (pin "P5") (pinfunction "A_4_P5") (pintype "bidirectional"))
    )
    (net (code "67") (name "/US1_NC") (class "Default")
      (node (ref "J14") (pin "7") (pinfunction "7_7") (pintype "passive"))
      (node (ref "U1") (pin "A9") (pinfunction "A9_A9") (pintype "bidirectional"))
      (node (ref "US1") (pin "P$3") (pinfunction "1_P$3") (pintype "passive"))
    )
    (net (code "68") (name "/US1_SIG") (class "Default")
      (node (ref "J14") (pin "8") (pinfunction "8_8") (pintype "passive"))
      (node (ref "U1") (pin "A8") (pinfunction "A8_A8") (pintype "bidirectional"))
      (node (ref "US1") (pin "P$4") (pinfunction "1_P$4") (pintype "passive"))
    )
    (net (code "69") (name "/US2_NC") (class "Default")
      (node (ref "J14") (pin "5") (pinfunction "5_5") (pintype "passive"))
      (node (ref "U1") (pin "A11") (pinfunction "A11_A11") (pintype "bidirectional"))
      (node (ref "US4") (pin "P$3") (pinfunction "1_P$3") (pintype "passive"))
    )
    (net (code "70") (name "/US2_SIG") (class "Default")
      (node (ref "J14") (pin "6") (pinfunction "6_6") (pintype "passive"))
      (node (ref "U1") (pin "A10") (pinfunction "A10_A10") (pintype "bidirectional"))
      (node (ref "US4") (pin "P$4") (pinfunction "1_P$4") (pintype "passive"))
    )
    (net (code "71") (name "/US3_NC") (class "Default")
      (node (ref "J14") (pin "3") (pinfunction "3_3") (pintype "passive"))
      (node (ref "U1") (pin "A13") (pinfunction "A13_A13") (pintype "bidirectional"))
      (node (ref "US2") (pin "P$3") (pinfunction "1_P$3") (pintype "passive"))
    )
    (net (code "72") (name "/US3_SIG") (class "Default")
      (node (ref "J14") (pin "4") (pinfunction "4_4") (pintype "passive"))
      (node (ref "U1") (pin "A12") (pinfunction "A12_A12") (pintype "bidirectional"))
      (node (ref "US2") (pin "P$4") (pinfunction "1_P$4") (pintype "passive"))
    )
    (net (code "73") (name "/US4_NC") (class "Default")
      (node (ref "J14") (pin "1") (pinfunction "1_1") (pintype "passive"))
      (node (ref "U1") (pin "A15") (pinfunction "A15_A15") (pintype "bidirectional"))
      (node (ref "US5") (pin "P$3") (pinfunction "1_P$3") (pintype "passive"))
    )
    (net (code "74") (name "/US4_SIG") (class "Default")
      (node (ref "J14") (pin "2") (pinfunction "2_2") (pintype "passive"))
      (node (ref "U1") (pin "A14") (pinfunction "A14_A14") (pintype "bidirectional"))
      (node (ref "US5") (pin "P$4") (pinfunction "1_P$4") (pintype "passive"))
    )
    (net (code "75") (name "/US5_NC") (class "Default")
      (node (ref "J13") (pin "1") (pinfunction "1_1") (pintype "passive"))
      (node (ref "U1") (pin "A7") (pinfunction "A7_A7") (pintype "bidirectional"))
      (node (ref "US3") (pin "P$3") (pinfunction "1_P$3") (pintype "passive"))
    )
    (net (code "76") (name "/US5_SIG") (class "Default")
      (node (ref "J13") (pin "2") (pinfunction "2_2") (pintype "passive"))
      (node (ref "U1") (pin "A6") (pinfunction "A6_A6") (pintype "bidirectional"))
      (node (ref "US3") (pin "P$4") (pinfunction "1_P$4") (pintype "passive"))
    )
    (net (code "77") (name "/VCC") (class "Default")
      (node (ref "BUCK") (pin "P3") (pinfunction "OUT+_P3") (pintype "bidirectional"))
      (node (ref "IMU_2") (pin "P$1") (pinfunction "1_P$1") (pintype "passive"))
      (node (ref "J1") (pin "1") (pinfunction "1_1") (pintype "passive"))
      (node (ref "J10") (pin "1") (pinfunction "1_1") (pintype "passive"))
      (node (ref "J11") (pin "1") (pinfunction "1_1") (pintype "passive"))
      (node (ref "J12") (pin "1") (pinfunction "1_1") (pintype "passive"))
      (node (ref "J2") (pin "1") (pinfunction "1_1") (pintype "passive"))
      (node (ref "J3") (pin "1") (pinfunction "1_1") (pintype "passive"))
      (node (ref "J4") (pin "1") (pinfunction "1_1") (pintype "passive"))
      (node (ref "J5") (pin "1") (pinfunction "1_1") (pintype "passive"))
      (node (ref "J6") (pin "1") (pinfunction "1_1") (pintype "passive"))
      (node (ref "J7") (pin "1") (pinfunction "1_1") (pintype "passive"))
      (node (ref "J8") (pin "1") (pinfunction "1_1") (pintype "passive"))
      (node (ref "J9") (pin "1") (pinfunction "1_1") (pintype "passive"))
      (node (ref "LED1") (pin "2") (pinfunction "VCC_2") (pintype "bidirectional"))
      (node (ref "NAVBOARD_2.0") (pin "P$3") (pinfunction "1_P$3") (pintype "passive"))
      (node (ref "OLED") (pin "P$1") (pinfunction "1_P$1") (pintype "passive"))
      (node (ref "SD1") (pin "5") (pinfunction "5_5") (pintype "passive"))
      (node (ref "US1") (pin "P$2") (pinfunction "1_P$2") (pintype "passive"))
      (node (ref "US2") (pin "P$2") (pinfunction "1_P$2") (pintype "passive"))
      (node (ref "US3") (pin "P$2") (pinfunction "1_P$2") (pintype "passive"))
      (node (ref "US4") (pin "P$2") (pinfunction "1_P$2") (pintype "passive"))
      (node (ref "US5") (pin "P$2") (pinfunction "1_P$2") (pintype "passive"))
    )
    (net (code "78") (name "GND") (class "Default")
      (node (ref "B3") (pin "4") (pinfunction "4_4") (pintype "passive"))
      (node (ref "B4") (pin "4") (pinfunction "4_4") (pintype "passive"))
      (node (ref "BUCK") (pin "P2") (pinfunction "IN-_P2") (pintype "bidirectional"))
      (node (ref "BUCK") (pin "P4") (pinfunction "OUT-_P4") (pintype "bidirectional"))
      (node (ref "C1") (pin "-") (pinfunction "-_-") (pintype "passive"))
      (node (ref "C2") (pin "-") (pinfunction "-_-") (pintype "passive"))
      (node (ref "C3") (pin "-") (pinfunction "-_-") (pintype "passive"))
      (node (ref "C4") (pin "-") (pinfunction "-_-") (pintype "passive"))
      (node (ref "C5") (pin "-") (pinfunction "-_-") (pintype "passive"))
      (node (ref "C6") (pin "-") (pinfunction "-_-") (pintype "passive"))
      (node (ref "C7") (pin "-") (pinfunction "-_-") (pintype "passive"))
      (node (ref "C8") (pin "-") (pinfunction "-_-") (pintype "passive"))
      (node (ref "C9") (pin "-") (pinfunction "-_-") (pintype "passive"))
      (node (ref "ESP1") (pin "P8") (pinfunction "GND_P8") (pintype "bidirectional"))
      (node (ref "IMU1") (pin "7") (pinfunction "7_7") (pintype "passive"))
      (node (ref "IMU_2") (pin "P$4") (pinfunction "1_P$4") (pintype "passive"))
      (node (ref "J1") (pin "2") (pinfunction "2_2") (pintype "passive"))
      (node (ref "J10") (pin "2") (pinfunction "2_2") (pintype "passive"))
      (node (ref "J11") (pin "2") (pinfunction "2_2") (pintype "passive"))
      (node (ref "J12") (pin "2") (pinfunction "2_2") (pintype "passive"))
      (node (ref "J2") (pin "2") (pinfunction "2_2") (pintype "passive"))
      (node (ref "J3") (pin "2") (pinfunction "2_2") (pintype "passive"))
      (node (ref "J4") (pin "2") (pinfunction "2_2") (pintype "passive"))
      (node (ref "J5") (pin "2") (pinfunction "2_2") (pintype "passive"))
      (node (ref "J6") (pin "2") (pinfunction "2_2") (pintype "passive"))
      (node (ref "J7") (pin "2") (pinfunction "2_2") (pintype "passive"))
      (node (ref "J8") (pin "2") (pinfunction "2_2") (pintype "passive"))
      (node (ref "J9") (pin "2") (pinfunction "2_2") (pintype "passive"))
      (node (ref "L1") (pin "K") (pinfunction "C_K") (pintype "passive"))
      (node (ref "L2") (pin "K") (pinfunction "C_K") (pintype "passive"))
      (node (ref "L3") (pin "K") (pinfunction "C_K") (pintype "passive"))
      (node (ref "M_GND") (pin "1") (pinfunction "P_1") (pintype "passive"))
      (node (ref "NAVBOARD_2.0") (pin "P$4") (pinfunction "1_P$4") (pintype "passive"))
      (node (ref "OLED") (pin "P$2") (pinfunction "1_P$2") (pintype "passive"))
      (node (ref "PWR") (pin "1") (pinfunction "1_1") (pintype "passive"))
      (node (ref "R9") (pin "1") (pinfunction "1_1") (pintype "passive"))
      (node (ref "RST") (pin "2") (pinfunction "2_2") (pintype "passive"))
      (node (ref "RST_ESP") (pin "2") (pinfunction "2_2") (pintype "passive"))
      (node (ref "SD1") (pin "6") (pinfunction "6_6") (pintype "passive"))
      (node (ref "U1") (pin "GND@0") (pinfunction "GND_GND@0") (pintype "bidirectional"))
      (node (ref "U1") (pin "GND@1") (pinfunction "GND_GND@1") (pintype "bidirectional"))
      (node (ref "U1") (pin "GND@2") (pinfunction "GND_GND@2") (pintype "bidirectional"))
      (node (ref "U1") (pin "GND@3") (pinfunction "GND_GND@3") (pintype "bidirectional"))
      (node (ref "U1") (pin "GND@4") (pinfunction "GND_GND@4") (pintype "bidirectional"))
      (node (ref "US1") (pin "P$1") (pinfunction "1_P$1") (pintype "passive"))
      (node (ref "US2") (pin "P$1") (pinfunction "1_P$1") (pintype "passive"))
      (node (ref "US3") (pin "P$1") (pinfunction "1_P$1") (pintype "passive"))
      (node (ref "US4") (pin "P$1") (pinfunction "1_P$1") (pintype "passive"))
      (node (ref "US5") (pin "P$1") (pinfunction "1_P$1") (pintype "passive"))
    )
    (net (code "79") (name "Net-(C1-Pad+)") (class "Default")
      (node (ref "C1") (pin "+") (pinfunction "+_+") (pintype "passive"))
      (node (ref "R1") (pin "2") (pinfunction "2_2") (pintype "passive"))
      (node (ref "SEL1") (pin "3") (pinfunction "3_3") (pintype "passive"))
    )
    (net (code "80") (name "Net-(C2-Pad+)") (class "Default")
      (node (ref "C2") (pin "+") (pinfunction "+_+") (pintype "passive"))
      (node (ref "R2") (pin "2") (pinfunction "2_2") (pintype "passive"))
      (node (ref "SEL2") (pin "3") (pinfunction "3_3") (pintype "passive"))
    )
    (net (code "81") (name "Net-(C3-Pad+)") (class "Default")
      (node (ref "C3") (pin "+") (pinfunction "+_+") (pintype "passive"))
      (node (ref "R3") (pin "2") (pinfunction "2_2") (pintype "passive"))
      (node (ref "SEL3") (pin "3") (pinfunction "3_3") (pintype "passive"))
    )
    (net (code "82") (name "Net-(C4-Pad+)") (class "Default")
      (node (ref "C4") (pin "+") (pinfunction "+_+") (pintype "passive"))
      (node (ref "R4") (pin "2") (pinfunction "2_2") (pintype "passive"))
      (node (ref "SEL4") (pin "3") (pinfunction "3_3") (pintype "passive"))
    )
    (net (code "83") (name "Net-(C5-Pad+)") (class "Default")
      (node (ref "C5") (pin "+") (pinfunction "+_+") (pintype "passive"))
      (node (ref "R5") (pin "2") (pinfunction "2_2") (pintype "passive"))
      (node (ref "SEL5") (pin "3") (pinfunction "3_3") (pintype "passive"))
    )
    (net (code "84") (name "Net-(C6-Pad+)") (class "Default")
      (node (ref "C6") (pin "+") (pinfunction "+_+") (pintype "passive"))
      (node (ref "R6") (pin "2") (pinfunction "2_2") (pintype "passive"))
      (node (ref "SEL6") (pin "3") (pinfunction "3_3") (pintype "passive"))
    )
    (net (code "85") (name "Net-(C7-Pad+)") (class "Default")
      (node (ref "C7") (pin "+") (pinfunction "+_+") (pintype "passive"))
      (node (ref "R7") (pin "2") (pinfunction "2_2") (pintype "passive"))
      (node (ref "SEL7") (pin "3") (pinfunction "3_3") (pintype "passive"))
    )
    (net (code "86") (name "Net-(C8-Pad+)") (class "Default")
      (node (ref "C8") (pin "+") (pinfunction "+_+") (pintype "passive"))
      (node (ref "R8") (pin "2") (pinfunction "2_2") (pintype "passive"))
      (node (ref "SEL8") (pin "3") (pinfunction "3_3") (pintype "passive"))
    )
    (net (code "87") (name "Net-(D1-C)") (class "Default")
      (node (ref "D1") (pin "K") (pinfunction "C_K") (pintype "passive"))
      (node (ref "R9") (pin "2") (pinfunction "2_2") (pintype "passive"))
    )
    (net (code "88") (name "Net-(ESP1-RST)") (class "Default")
      (node (ref "ESP1") (pin "P0") (pinfunction "RST_P0") (pintype "bidirectional"))
      (node (ref "RST_ESP") (pin "3") (pinfunction "3_3") (pintype "passive"))
    )
    (net (code "89") (name "Net-(IMU1_SCL_SEL-1)") (class "Default")
      (node (ref "IMU1") (pin "6") (pinfunction "6_6") (pintype "passive"))
      (node (ref "IMU1_SCL_SEL") (pin "P2") (pinfunction "1_P2") (pintype "bidirectional"))
    )
    (net (code "90") (name "Net-(IMU1_SDA_SEL-1)") (class "Default")
      (node (ref "IMU1") (pin "5") (pinfunction "5_5") (pintype "passive"))
      (node (ref "IMU1_SDA_SEL") (pin "P2") (pinfunction "1_P2") (pintype "bidirectional"))
    )
    (net (code "91") (name "Net-(IMU2_SCL_SEL-1)") (class "Default")
      (node (ref "IMU2_SCL_SEL") (pin "P2") (pinfunction "1_P2") (pintype "bidirectional"))
      (node (ref "IMU_2") (pin "P$3") (pinfunction "1_P$3") (pintype "passive"))
    )
    (net (code "92") (name "Net-(IMU2_SDA_SEL-1)") (class "Default")
      (node (ref "IMU2_SDA_SEL") (pin "P2") (pinfunction "1_P2") (pintype "bidirectional"))
      (node (ref "IMU_2") (pin "P$2") (pinfunction "1_P$2") (pintype "passive"))
    )
    (net (code "93") (name "Net-(J13-Pad5)") (class "Default")
      (node (ref "J13") (pin "5") (pinfunction "5_5") (pintype "passive"))
      (node (ref "U1") (pin "A3") (pinfunction "A3_A3") (pintype "bidirectional"))
    )
    (net (code "94") (name "Net-(J13-Pad6)") (class "Default")
      (node (ref "J13") (pin "6") (pinfunction "6_6") (pintype "passive"))
      (node (ref "U1") (pin "A2") (pinfunction "A2_A2") (pintype "bidirectional"))
    )
    (net (code "95") (name "Net-(L1-PadA)") (class "Default")
      (node (ref "L1") (pin "A") (pinfunction "A_A") (pintype "passive"))
      (node (ref "R13") (pin "1") (pinfunction "1_1") (pintype "passive"))
    )
    (net (code "96") (name "Net-(L2-PadA)") (class "Default")
      (node (ref "L2") (pin "A") (pinfunction "A_A") (pintype "passive"))
      (node (ref "R14") (pin "1") (pinfunction "1_1") (pintype "passive"))
    )
    (net (code "97") (name "Net-(L3-PadA)") (class "Default")
      (node (ref "L3") (pin "A") (pinfunction "A_A") (pintype "passive"))
      (node (ref "R15") (pin "1") (pinfunction "1_1") (pintype "passive"))
    )
    (net (code "98") (name "Net-(LED1-BLUE)") (class "Default")
      (node (ref "LED1") (pin "4") (pinfunction "BLUE_4") (pintype "bidirectional"))
      (node (ref "R10") (pin "1") (pinfunction "1_1") (pintype "passive"))
    )
    (net (code "99") (name "Net-(LED1-GREEN)") (class "Default")
      (node (ref "LED1") (pin "3") (pinfunction "GREEN_3") (pintype "bidirectional"))
      (node (ref "R11") (pin "1") (pinfunction "1_1") (pintype "passive"))
    )
    (net (code "100") (name "Net-(LED1-RED)") (class "Default")
      (node (ref "LED1") (pin "1") (pinfunction "RED_1") (pintype "bidirectional"))
      (node (ref "R12") (pin "1") (pinfunction "1_1") (pintype "passive"))
    )
    (net (code "101") (name "Net-(MASTER-IN)") (class "Default")
      (node (ref "MASTER") (pin "1") (pinfunction "IN_1") (pintype "bidirectional"))
      (node (ref "PWR") (pin "2") (pinfunction "2_2") (pintype "passive"))
    )
    (net (code "102") (name "Net-(MDR1A-1)") (class "Default")
      (node (ref "MDR1") (pin "P$1") (pinfunction "1_P$1") (pintype "passive"))
      (node (ref "SEL1") (pin "2") (pinfunction "2_2") (pintype "passive"))
    )
    (net (code "103") (name "Net-(MDR2A-1)") (class "Default")
      (node (ref "MDR2") (pin "P$1") (pinfunction "1_P$1") (pintype "passive"))
      (node (ref "SEL2") (pin "2") (pinfunction "2_2") (pintype "passive"))
    )
    (net (code "104") (name "Net-(MDR3A-1)") (class "Default")
      (node (ref "MDR3") (pin "P$1") (pinfunction "1_P$1") (pintype "passive"))
      (node (ref "SEL3") (pin "2") (pinfunction "2_2") (pintype "passive"))
    )
    (net (code "105") (name "Net-(MDR4A-1)") (class "Default")
      (node (ref "MDR4") (pin "P$1") (pinfunction "1_P$1") (pintype "passive"))
      (node (ref "SEL4") (pin "2") (pinfunction "2_2") (pintype "passive"))
    )
    (net (code "106") (name "Net-(MDR5A-1)") (class "Default")
      (node (ref "MDR5") (pin "P$1") (pinfunction "1_P$1") (pintype "passive"))
      (node (ref "SEL5") (pin "2") (pinfunction "2_2") (pintype "passive"))
    )
    (net (code "107") (name "Net-(MDR6A-1)") (class "Default")
      (node (ref "MDR6") (pin "P$1") (pinfunction "1_P$1") (pintype "passive"))
      (node (ref "SEL6") (pin "2") (pinfunction "2_2") (pintype "passive"))
    )
    (net (code "108") (name "Net-(MDR7A-1)") (class "Default")
      (node (ref "MDR7") (pin "P$1") (pinfunction "1_P$1") (pintype "passive"))
      (node (ref "SEL7") (pin "2") (pinfunction "2_2") (pintype "passive"))
    )
    (net (code "109") (name "Net-(MDR8A-1)") (class "Default")
      (node (ref "MDR8") (pin "P$1") (pinfunction "1_P$1") (pintype "passive"))
      (node (ref "SEL8") (pin "2") (pinfunction "2_2") (pintype "passive"))
    )
    (net (code "110") (name "Net-(U$3-1)") (class "Default")
      (node (ref "U$3") (pin "P2") (pinfunction "1_P2") (pintype "bidirectional"))
      (node (ref "U1") (pin "0") (pinfunction "0(RX0)_0") (pintype "bidirectional"))
    )
    (net (code "111") (name "Net-(U$3-3)") (class "Default")
      (node (ref "J15") (pin "8") (pinfunction "8_8") (pintype "passive"))
      (node (ref "U$3") (pin "P3") (pinfunction "3_P3") (pintype "bidirectional"))
    )
    (net (code "112") (name "Net-(U$4-1)") (class "Default")
      (node (ref "U$4") (pin "P2") (pinfunction "1_P2") (pintype "bidirectional"))
      (node (ref "U1") (pin "1") (pinfunction "1(TX0)_1") (pintype "bidirectional"))
    )
    (net (code "113") (name "Net-(U$4-3)") (class "Default")
      (node (ref "J15") (pin "7") (pinfunction "7_7") (pintype "passive"))
      (node (ref "U$4") (pin "P3") (pinfunction "3_P3") (pintype "bidirectional"))
    )
    (net (code "114") (name "Net-(U1-A0(RX0))") (class "Default")
      (node (ref "J13") (pin "8") (pinfunction "8_8") (pintype "passive"))
      (node (ref "U1") (pin "A0") (pinfunction "A0(RX0)_A0") (pintype "bidirectional"))
    )
    (net (code "115") (name "Net-(U1-A1(TX0))") (class "Default")
      (node (ref "J13") (pin "7") (pinfunction "7_7") (pintype "passive"))
      (node (ref "U1") (pin "A1") (pinfunction "A1(TX0)_A1") (pintype "bidirectional"))
    )
    (net (code "116") (name "unconnected-(B3-Pad2)") (class "Default")
      (node (ref "B3") (pin "2") (pinfunction "2_2") (pintype "passive"))
    )
    (net (code "117") (name "unconnected-(B3-Pad3)") (class "Default")
      (node (ref "B3") (pin "3") (pinfunction "3_3") (pintype "passive"))
    )
    (net (code "118") (name "unconnected-(B4-Pad2)") (class "Default")
      (node (ref "B4") (pin "2") (pinfunction "2_2") (pintype "passive"))
    )
    (net (code "119") (name "unconnected-(B4-Pad3)") (class "Default")
      (node (ref "B4") (pin "3") (pinfunction "3_3") (pintype "passive"))
    )
    (net (code "120") (name "unconnected-(ESP1-0-PadP11)") (class "Default")
      (node (ref "ESP1") (pin "P11") (pinfunction "0_P11") (pintype "bidirectional"))
    )
    (net (code "121") (name "unconnected-(ESP1-2-PadP10)") (class "Default")
      (node (ref "ESP1") (pin "P10") (pinfunction "2_P10") (pintype "bidirectional"))
    )
    (net (code "122") (name "unconnected-(ESP1-12-PadP5)") (class "Default")
      (node (ref "ESP1") (pin "P5") (pinfunction "12_P5") (pintype "bidirectional"))
    )
    (net (code "123") (name "unconnected-(ESP1-15-PadP9)") (class "Default")
      (node (ref "ESP1") (pin "P9") (pinfunction "15_P9") (pintype "bidirectional"))
    )
    (net (code "124") (name "unconnected-(ESP1-16-PadP3)") (class "Default")
      (node (ref "ESP1") (pin "P3") (pinfunction "16_P3") (pintype "bidirectional"))
    )
    (net (code "125") (name "unconnected-(ESP1-ADC-PadP1)") (class "Default")
      (node (ref "ESP1") (pin "P1") (pinfunction "ADC_P1") (pintype "bidirectional"))
    )
    (net (code "126") (name "unconnected-(ESP1-EN-PadP2)") (class "Default")
      (node (ref "ESP1") (pin "P2") (pinfunction "EN_P2") (pintype "bidirectional"))
    )
    (net (code "127") (name "unconnected-(IMU1-Pad1)") (class "Default")
      (node (ref "IMU1") (pin "1") (pinfunction "1_1") (pintype "passive"))
    )
    (net (code "128") (name "unconnected-(IMU1-Pad2)") (class "Default")
      (node (ref "IMU1") (pin "2") (pinfunction "2_2") (pintype "passive"))
    )
    (net (code "129") (name "unconnected-(IMU1-Pad3)") (class "Default")
      (node (ref "IMU1") (pin "3") (pinfunction "3_3") (pintype "passive"))
    )
    (net (code "130") (name "unconnected-(IMU1-Pad4)") (class "Default")
      (node (ref "IMU1") (pin "4") (pinfunction "4_4") (pintype "passive"))
    )
    (net (code "131") (name "unconnected-(RST-Pad1)") (class "Default")
      (node (ref "RST") (pin "1") (pinfunction "1_1") (pintype "passive"))
    )
    (net (code "132") (name "unconnected-(RST-Pad4)") (class "Default")
      (node (ref "RST") (pin "4") (pinfunction "4_4") (pintype "passive"))
    )
    (net (code "133") (name "unconnected-(RST_ESP-Pad1)") (class "Default")
      (node (ref "RST_ESP") (pin "1") (pinfunction "1_1") (pintype "passive"))
    )
    (net (code "134") (name "unconnected-(RST_ESP-Pad4)") (class "Default")
      (node (ref "RST_ESP") (pin "4") (pinfunction "4_4") (pintype "passive"))
    )
    (net (code "135") (name "unconnected-(U$3-2-PadP1)") (class "Default")
      (node (ref "U$3") (pin "P1") (pinfunction "2_P1") (pintype "bidirectional"))
    )
    (net (code "136") (name "unconnected-(U$4-2-PadP1)") (class "Default")
      (node (ref "U$4") (pin "P1") (pinfunction "2_P1") (pintype "bidirectional"))
    )
    (net (code "137") (name "unconnected-(U$9-A_1-PadP0)") (class "Default")
      (node (ref "U$9") (pin "P0") (pinfunction "A_1_P0") (pintype "bidirectional"))
    )
    (net (code "138") (name "unconnected-(U$9-A_2-PadP1)") (class "Default")
      (node (ref "U$9") (pin "P1") (pinfunction "A_2_P1") (pintype "bidirectional"))
    )
    (net (code "139") (name "unconnected-(U$9-A_3-PadP4)") (class "Default")
      (node (ref "U$9") (pin "P4") (pinfunction "A_3_P4") (pintype "bidirectional"))
    )
    (net (code "140") (name "unconnected-(U$9-B_1-PadP6)") (class "Default")
      (node (ref "U$9") (pin "P6") (pinfunction "B_1_P6") (pintype "bidirectional"))
    )
    (net (code "141") (name "unconnected-(U$9-B_2-PadP7)") (class "Default")
      (node (ref "U$9") (pin "P7") (pinfunction "B_2_P7") (pintype "bidirectional"))
    )
    (net (code "142") (name "unconnected-(U$9-B_3-PadP10)") (class "Default")
      (node (ref "U$9") (pin "P10") (pinfunction "B_3_P10") (pintype "bidirectional"))
    )
    (net (code "143") (name "unconnected-(U$9-C_1-PadP12)") (class "Default")
      (node (ref "U$9") (pin "P12") (pinfunction "C_1_P12") (pintype "bidirectional"))
    )
    (net (code "144") (name "unconnected-(U$9-C_2-PadP13)") (class "Default")
      (node (ref "U$9") (pin "P13") (pinfunction "C_2_P13") (pintype "bidirectional"))
    )
    (net (code "145") (name "unconnected-(U$9-C_3-PadP16)") (class "Default")
      (node (ref "U$9") (pin "P16") (pinfunction "C_3_P16") (pintype "bidirectional"))
    )
    (net (code "146") (name "unconnected-(U$9-D_1-PadP23)") (class "Default")
      (node (ref "U$9") (pin "P23") (pinfunction "D_1_P23") (pintype "bidirectional"))
    )
    (net (code "147") (name "unconnected-(U$9-D_2-PadP22)") (class "Default")
      (node (ref "U$9") (pin "P22") (pinfunction "D_2_P22") (pintype "bidirectional"))
    )
    (net (code "148") (name "unconnected-(U$9-D_3-PadP19)") (class "Default")
      (node (ref "U$9") (pin "P19") (pinfunction "D_3_P19") (pintype "bidirectional"))
    )
    (net (code "149") (name "unconnected-(U$9-E_1-PadP29)") (class "Default")
      (node (ref "U$9") (pin "P29") (pinfunction "E_1_P29") (pintype "bidirectional"))
    )
    (net (code "150") (name "unconnected-(U$9-E_2-PadP28)") (class "Default")
      (node (ref "U$9") (pin "P28") (pinfunction "E_2_P28") (pintype "bidirectional"))
    )
    (net (code "151") (name "unconnected-(U$9-E_3-PadP25)") (class "Default")
      (node (ref "U$9") (pin "P25") (pinfunction "E_3_P25") (pintype "bidirectional"))
    )
    (net (code "152") (name "unconnected-(U$9-F_1-PadP35)") (class "Default")
      (node (ref "U$9") (pin "P35") (pinfunction "F_1_P35") (pintype "bidirectional"))
    )
    (net (code "153") (name "unconnected-(U$9-F_2-PadP34)") (class "Default")
      (node (ref "U$9") (pin "P34") (pinfunction "F_2_P34") (pintype "bidirectional"))
    )
    (net (code "154") (name "unconnected-(U$9-F_3-PadP31)") (class "Default")
      (node (ref "U$9") (pin "P31") (pinfunction "F_3_P31") (pintype "bidirectional"))
    )
    (net (code "155") (name "unconnected-(U1-5V-Pad5V@0)") (class "Default")
      (node (ref "U1") (pin "5V@0") (pinfunction "5V_5V@0") (pintype "bidirectional"))
    )
    (net (code "156") (name "unconnected-(U1-5V-Pad5V@1)") (class "Default")
      (node (ref "U1") (pin "5V@1") (pinfunction "5V_5V@1") (pintype "bidirectional"))
    )
    (net (code "157") (name "unconnected-(U1-5V-Pad5V@2)") (class "Default")
      (node (ref "U1") (pin "5V@2") (pinfunction "5V_5V@2") (pintype "bidirectional"))
    )
    (net (code "158") (name "unconnected-(U1-PadAREF)") (class "Default")
      (node (ref "U1") (pin "AREF") (pinfunction "AREF_AREF") (pintype "bidirectional"))
    )
  )
)
